# CAN.net
KiCad netlist of a schematic drawn in Altium Designer
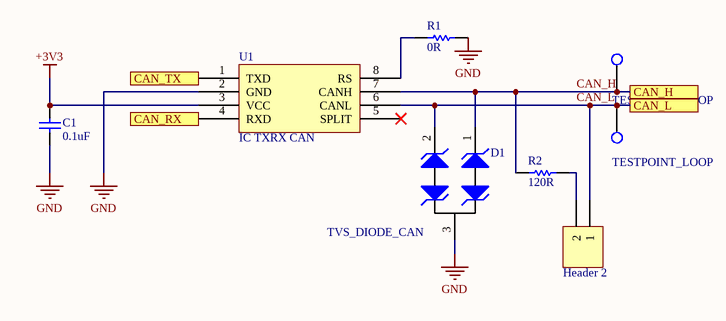
[diagram p0: CAN.SchDoc]

(export (version "E")
  (design (tool "Eeschema 10.0.6"))
  (components
    (comp (ref "1")
      (value "Header 2")
      (footprint "HDR1X2")
      (description "Header, 2-Pin")
      (fields (field (name "PUBLISHER") "Altium Limited"))
      (libsource (lib "Miscellaneous Connectors") (part "Header 2"))
    )
    (comp (ref "C1")
      (value "0.1uF")
      (footprint "CAPC0603(1608)55_N")
      (description "CAP CER 0.1UF 16V X7R 0603")
      (fields (field (name "MANUFACTURER") "Yageo") (field (name "MPN") "CC0603KRX7R7BB104"))
      (libsource (lib "UWRT_Schematic_Library_2019") (part "CAP_0.1uF_16V_0603"))
    )
    (comp (ref "CANH1")
      (value "TESTPOINT_LOOP")
      (footprint "TESTPOINT_LOOP")
      (libsource (lib "UWRT_Schematic_Library_2019") (part "TESTPOINT_LOOP"))
    )
    (comp (ref "CANL1")
      (value "TESTPOINT_LOOP")
      (footprint "TESTPOINT_LOOP")
      (libsource (lib "UWRT_Schematic_Library_2019") (part "TESTPOINT_LOOP"))
    )
    (comp (ref "D1")
      (value "TVS_DIODE_CAN")
      (footprint "UWRT_Footprint_Library_2019:TVS_DIODE_CAN")
      (description "TVS DIODE 24V 41V SOT323-3")
      (fields (field (name "MANUFACTURER") "Nexperia USA Inc.") (field (name "MPN") "PESD2CAN,215"))
      (libsource (lib "UWRT_Schematic_Library_2019") (part "TVS_DIODE_CAN"))
    )
    (comp (ref "R1")
      (value "0R")
      (footprint "RESC0603(1608)_N")
      (description "RES SMD 0 OHM JUMPER 1/10W 0603")
      (fields (field (name "MANUFACTURER") "Yageo") (field (name "MPN") "RC0603JR-070RL"))
      (libsource (lib "UWRT_Schematic_Library_2019") (part "RES_0R_0603"))
    )
    (comp (ref "R2")
      (value "120R")
      (footprint "RESC0603(1608)_N")
      (description "RES SMD 120 OHM 5% 1/10W 0603")
      (fields (field (name "MANUFACTURER") "Yageo") (field (name "TOLERANCE") "5%"))
      (libsource (lib "UWRT_Schematic_Library_2019") (part "RES_120R_0603"))
    )
    (comp (ref "U1")
      (value "IC TXRX CAN")
      (footprint "LT-S8_N")
      (description "IC TXRX CAN 4MBPS 8SO")
      (fields (field (name "MANUFACTURER") "Linear Technologies") (field (name "MPN") "LTC2875IS8#PBF"))
      (libsource (lib "UWRT_Schematic_Library_2019") (part "LTC2875"))
    )
  )
  (nets
    (net (code "1") (name "+3V3") (class "Default")
      (node (ref "C1") (pin "2") (pinfunction "2_2") (pintype "passive"))
      (node (ref "U1") (pin "3") (pinfunction "VCC_3") (pintype "passive"))
    )
    (net (code "2") (name "/CAN_H") (class "Default")
      (node (ref "CANH1") (pin "1") (pinfunction "=value_1") (pintype "passive"))
      (node (ref "D1") (pin "1") (pinfunction "1_1") (pintype "passive"))
      (node (ref "R2") (pin "1") (pinfunction "1_1") (pintype "passive"))
      (node (ref "U1") (pin "7") (pinfunction "CANH_7") (pintype "passive"))
    )
    (net (code "3") (name "/CAN_L") (class "Default")
      (node (ref "1") (pin "1") (pinfunction "1_1") (pintype "passive"))
      (node (ref "CANL1") (pin "1") (pinfunction "=value_1") (pintype "passive"))
      (node (ref "D1") (pin "2") (pinfunction "2_2") (pintype "passive"))
      (node (ref "U1") (pin "6") (pinfunction "CANL_6") (pintype "passive"))
    )
    (net (code "4") (name "/CAN_RX") (class "Default")
      (node (ref "U1") (pin "4") (pinfunction "RXD_4") (pintype "passive"))
    )
    (net (code "5") (name "/CAN_TX") (class "Default")
      (node (ref "U1") (pin "1") (pinfunction "TXD_1") (pintype "passive"))
    )
    (net (code "6") (name "GND") (class "Default")
      (node (ref "C1") (pin "1") (pinfunction "1_1") (pintype "passive"))
      (node (ref "D1") (pin "3") (pinfunction "3_3") (pintype "passive"))
      (node (ref "R1") (pin "2") (pinfunction "2_2") (pintype "passive"))
      (node (ref "U1") (pin "2") (pinfunction "GND_2") (pintype "passive"))
    )
    (net (code "7") (name "Net-(1-Pad2)") (class "Default")
      (node (ref "1") (pin "2") (pinfunction "2_2") (pintype "passive"))
      (node (ref "R2") (pin "2") (pinfunction "2_2") (pintype "passive"))
    )
    (net (code "8") (name "Net-(U1-RS)") (class "Default")
      (node (ref "R1") (pin "1") (pinfunction "1_1") (pintype "passive"))
      (node (ref "U1") (pin "8") (pinfunction "RS_8") (pintype "passive"))
    )
    (net (code "9") (name "unconnected-(U1-SPLIT-Pad5)") (class "Default")
      (node (ref "U1") (pin "5") (pinfunction "SPLIT_5") (pintype "passive+no_connect"))
    )
  )
)
